# antenna.net
KiCad netlist of a schematic drawn in EAGLE
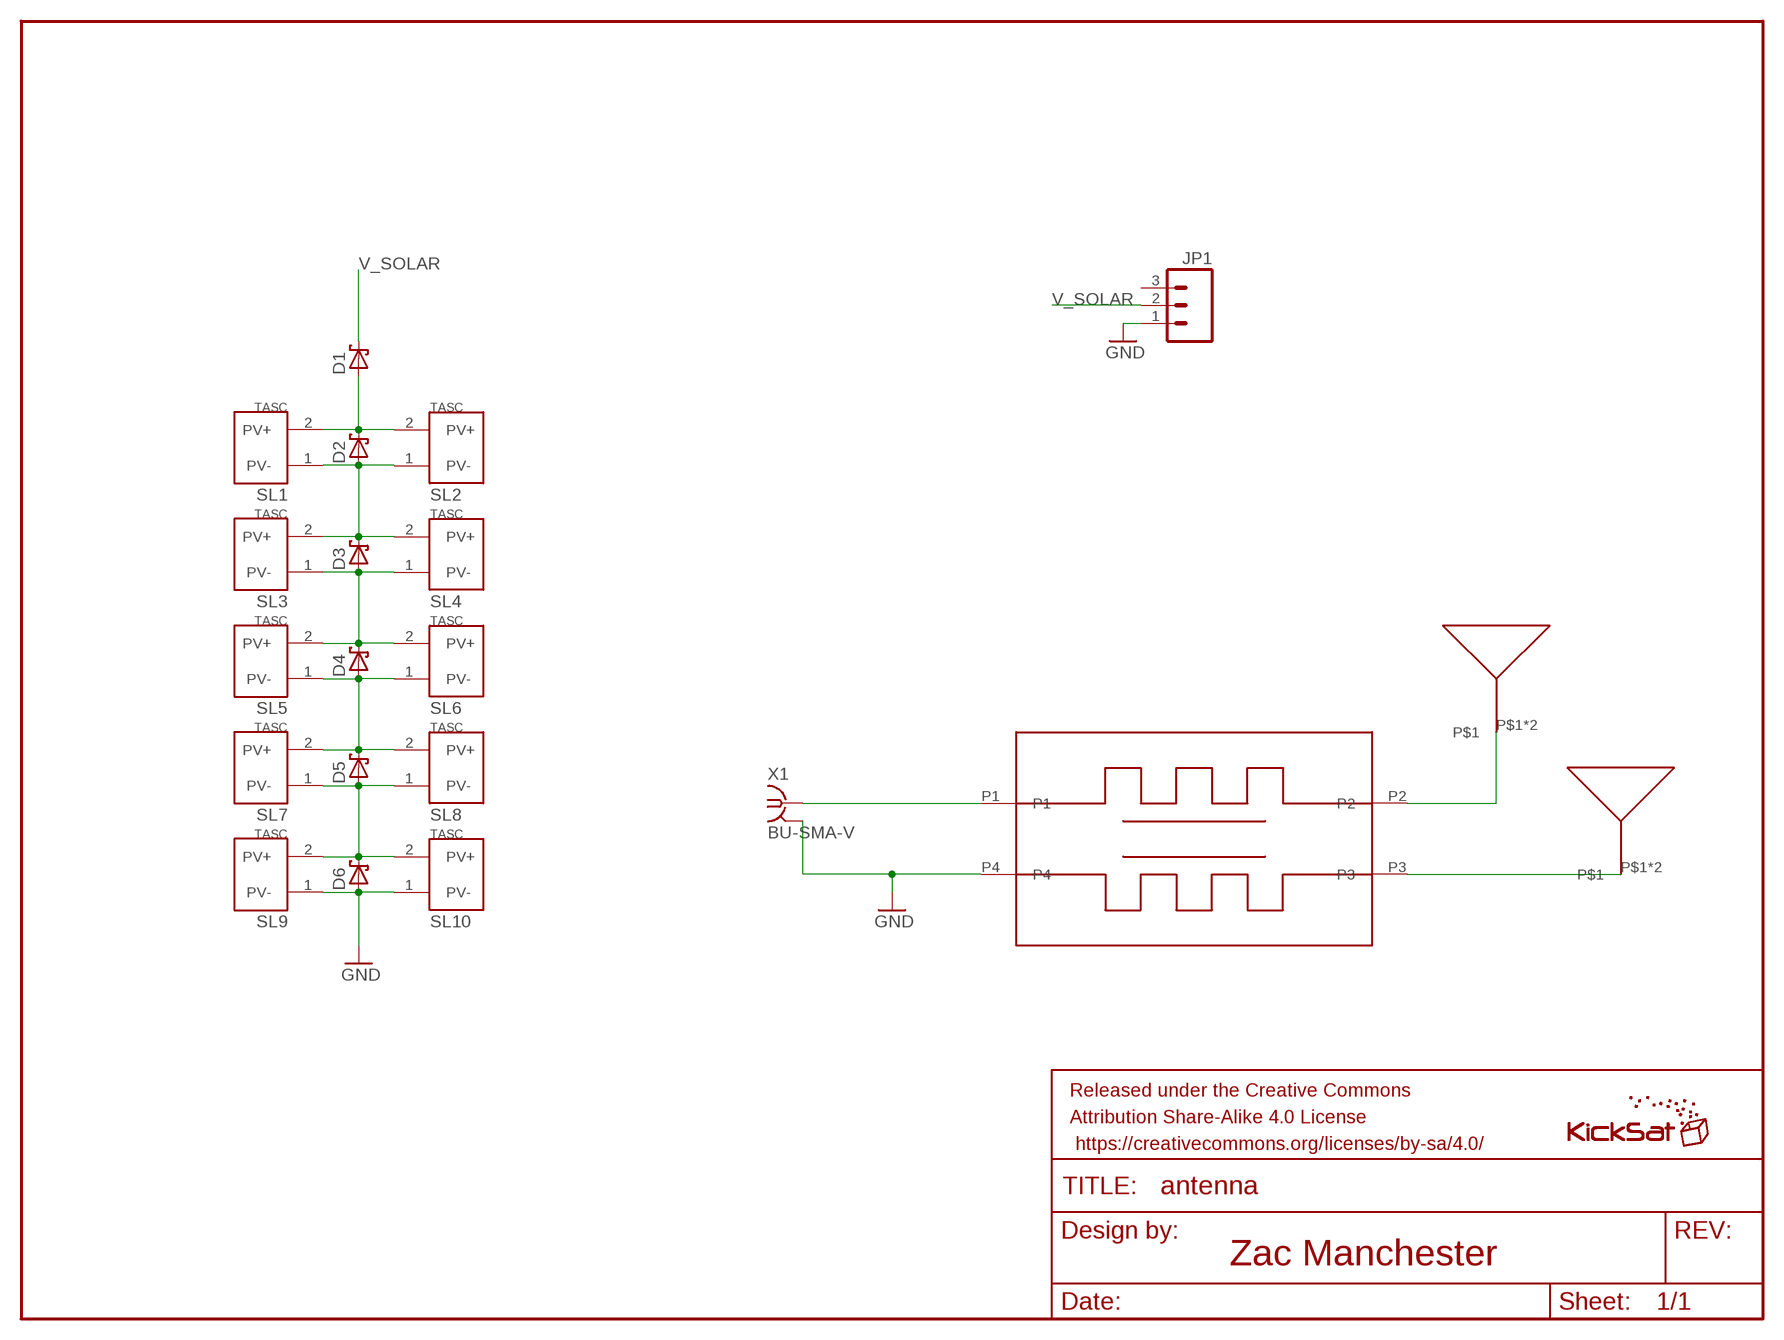
[diagram p0: schematic, sheet 1]

(export (version "E")
  (design (tool "Eeschema 10.0.6"))
  (components
    (comp (ref "B1")
      (value "BALUN")
      (footprint "eagle-import:BALUN")
      (libsource (lib "eagle-import") (part "BALUN"))
    )
    (comp (ref "D1")
      (value "SB_DIODE")
      (footprint "eagle-import:SB_DIODE")
      (libsource (lib "eagle-import") (part "SB_DIODE"))
    )
    (comp (ref "D2")
      (value "SB_DIODE")
      (footprint "eagle-import:SB_DIODE")
      (libsource (lib "eagle-import") (part "SB_DIODE"))
    )
    (comp (ref "D3")
      (value "SB_DIODE")
      (footprint "eagle-import:SB_DIODE")
      (libsource (lib "eagle-import") (part "SB_DIODE"))
    )
    (comp (ref "D4")
      (value "SB_DIODE")
      (footprint "eagle-import:SB_DIODE")
      (libsource (lib "eagle-import") (part "SB_DIODE"))
    )
    (comp (ref "D5")
      (value "SB_DIODE")
      (footprint "eagle-import:SB_DIODE")
      (libsource (lib "eagle-import") (part "SB_DIODE"))
    )
    (comp (ref "D6")
      (value "SB_DIODE")
      (footprint "eagle-import:SB_DIODE")
      (libsource (lib "eagle-import") (part "SB_DIODE"))
    )
    (comp (ref "FRAME1")
      (value "FRAME-LETTER")
      (footprint "eagle-import:CREATIVE_COMMONS")
      (libsource (lib "eagle-import") (part "FRAME-LETTER"))
    )
    (comp (ref "JP1")
      (value "M03POLAR_LOCK")
      (footprint "eagle-import:MOLEX-1X3_LOCK")
      (libsource (lib "eagle-import") (part "M03POLAR_LOCK"))
    )
    (comp (ref "SL1")
      (value "SOLAR_CELL")
      (footprint "eagle-import:SOLAR_CELL")
      (libsource (lib "eagle-import") (part "SOLAR_CELL"))
    )
    (comp (ref "SL2")
      (value "SOLAR_CELL")
      (footprint "eagle-import:SOLAR_CELL")
      (libsource (lib "eagle-import") (part "SOLAR_CELL"))
    )
    (comp (ref "SL3")
      (value "SOLAR_CELL")
      (footprint "eagle-import:SOLAR_CELL")
      (libsource (lib "eagle-import") (part "SOLAR_CELL"))
    )
    (comp (ref "SL4")
      (value "SOLAR_CELL")
      (footprint "eagle-import:SOLAR_CELL")
      (libsource (lib "eagle-import") (part "SOLAR_CELL"))
    )
    (comp (ref "SL5")
      (value "SOLAR_CELL")
      (footprint "eagle-import:SOLAR_CELL")
      (libsource (lib "eagle-import") (part "SOLAR_CELL"))
    )
    (comp (ref "SL6")
      (value "SOLAR_CELL")
      (footprint "eagle-import:SOLAR_CELL")
      (libsource (lib "eagle-import") (part "SOLAR_CELL"))
    )
    (comp (ref "SL7")
      (value "SOLAR_CELL")
      (footprint "eagle-import:SOLAR_CELL")
      (libsource (lib "eagle-import") (part "SOLAR_CELL"))
    )
    (comp (ref "SL8")
      (value "SOLAR_CELL")
      (footprint "eagle-import:SOLAR_CELL")
      (libsource (lib "eagle-import") (part "SOLAR_CELL"))
    )
    (comp (ref "SL9")
      (value "SOLAR_CELL")
      (footprint "eagle-import:SOLAR_CELL")
      (libsource (lib "eagle-import") (part "SOLAR_CELL"))
    )
    (comp (ref "SL10")
      (value "SOLAR_CELL")
      (footprint "eagle-import:SOLAR_CELL")
      (libsource (lib "eagle-import") (part "SOLAR_CELL"))
    )
    (comp (ref "U$1")
      (value "TAPEANTENNA")
      (footprint "eagle-import:TAPEANTENNA")
      (libsource (lib "eagle-import") (part "TAPEANTENNA"))
    )
    (comp (ref "U$2")
      (value "TAPEANTENNA")
      (footprint "eagle-import:TAPEANTENNA")
      (libsource (lib "eagle-import") (part "TAPEANTENNA"))
    )
    (comp (ref "U$3")
      (value "KICKSAT_LOGO")
      (footprint "eagle-import:KICKSAT_LOGO")
      (libsource (lib "eagle-import") (part "KICKSAT_LOGO"))
    )
    (comp (ref "X1")
      (value "BU-SMA-V")
      (footprint "eagle-import:BU-SMA-V")
      (libsource (lib "eagle-import") (part "BU-SMA-V"))
    )
  )
  (nets
    (net (code "1") (name "/V_SOLAR") (class "Default")
      (node (ref "D1") (pin "NEG") (pinfunction "NEG_NEG") (pintype "passive"))
      (node (ref "JP1") (pin "2") (pinfunction "2_2") (pintype "passive"))
    )
    (net (code "2") (name "GND") (class "Default")
      (node (ref "B1") (pin "P4") (pinfunction "P4_P4") (pintype "bidirectional"))
      (node (ref "D6") (pin "POS") (pinfunction "POS_POS") (pintype "passive"))
      (node (ref "JP1") (pin "1") (pinfunction "1_1") (pintype "passive"))
      (node (ref "SL10") (pin "1") (pinfunction "PV-_1") (pintype "bidirectional"))
      (node (ref "SL9") (pin "1") (pinfunction "PV-_1") (pintype "bidirectional"))
      (node (ref "X1") (pin "2") (pinfunction "2_2") (pintype "passive"))
      (node (ref "X1") (pin "3") (pinfunction "2_3") (pintype "passive"))
      (node (ref "X1") (pin "4") (pinfunction "2_4") (pintype "passive"))
      (node (ref "X1") (pin "5") (pinfunction "2_5") (pintype "passive"))
    )
    (net (code "3") (name "Net-(B1-PadP1)") (class "Default")
      (node (ref "B1") (pin "P1") (pinfunction "P1_P1") (pintype "bidirectional"))
      (node (ref "X1") (pin "1") (pinfunction "1_1") (pintype "passive"))
    )
    (net (code "4") (name "Net-(B1-PadP2)") (class "Default")
      (node (ref "B1") (pin "P2") (pinfunction "P2_P2") (pintype "bidirectional"))
      (node (ref "U$1") (pin "P$1") (pinfunction "P$1_P$1") (pintype "bidirectional"))
      (node (ref "U$1") (pin "P$2") (pinfunction "P$1_P$2") (pintype "bidirectional"))
    )
    (net (code "5") (name "Net-(B1-PadP3)") (class "Default")
      (node (ref "B1") (pin "P3") (pinfunction "P3_P3") (pintype "bidirectional"))
      (node (ref "U$2") (pin "P$1") (pinfunction "P$1_P$1") (pintype "bidirectional"))
      (node (ref "U$2") (pin "P$2") (pinfunction "P$1_P$2") (pintype "bidirectional"))
    )
    (net (code "6") (name "Net-(SL1-PV+)") (class "Default")
      (node (ref "D1") (pin "POS") (pinfunction "POS_POS") (pintype "passive"))
      (node (ref "D2") (pin "NEG") (pinfunction "NEG_NEG") (pintype "passive"))
      (node (ref "SL1") (pin "2") (pinfunction "PV+_2") (pintype "bidirectional"))
      (node (ref "SL2") (pin "2") (pinfunction "PV+_2") (pintype "bidirectional"))
    )
    (net (code "7") (name "Net-(SL1-PV-)") (class "Default")
      (node (ref "D2") (pin "POS") (pinfunction "POS_POS") (pintype "passive"))
      (node (ref "D3") (pin "NEG") (pinfunction "NEG_NEG") (pintype "passive"))
      (node (ref "SL1") (pin "1") (pinfunction "PV-_1") (pintype "bidirectional"))
      (node (ref "SL2") (pin "1") (pinfunction "PV-_1") (pintype "bidirectional"))
      (node (ref "SL3") (pin "2") (pinfunction "PV+_2") (pintype "bidirectional"))
      (node (ref "SL4") (pin "2") (pinfunction "PV+_2") (pintype "bidirectional"))
    )
    (net (code "8") (name "Net-(SL3-PV-)") (class "Default")
      (node (ref "D3") (pin "POS") (pinfunction "POS_POS") (pintype "passive"))
      (node (ref "D4") (pin "NEG") (pinfunction "NEG_NEG") (pintype "passive"))
      (node (ref "SL3") (pin "1") (pinfunction "PV-_1") (pintype "bidirectional"))
      (node (ref "SL4") (pin "1") (pinfunction "PV-_1") (pintype "bidirectional"))
      (node (ref "SL5") (pin "2") (pinfunction "PV+_2") (pintype "bidirectional"))
      (node (ref "SL6") (pin "2") (pinfunction "PV+_2") (pintype "bidirectional"))
    )
    (net (code "9") (name "Net-(SL5-PV-)") (class "Default")
      (node (ref "D4") (pin "POS") (pinfunction "POS_POS") (pintype "passive"))
      (node (ref "D5") (pin "NEG") (pinfunction "NEG_NEG") (pintype "passive"))
      (node (ref "SL5") (pin "1") (pinfunction "PV-_1") (pintype "bidirectional"))
      (node (ref "SL6") (pin "1") (pinfunction "PV-_1") (pintype "bidirectional"))
      (node (ref "SL7") (pin "2") (pinfunction "PV+_2") (pintype "bidirectional"))
      (node (ref "SL8") (pin "2") (pinfunction "PV+_2") (pintype "bidirectional"))
    )
    (net (code "10") (name "Net-(SL10-PV+)") (class "Default")
      (node (ref "D5") (pin "POS") (pinfunction "POS_POS") (pintype "passive"))
      (node (ref "D6") (pin "NEG") (pinfunction "NEG_NEG") (pintype "passive"))
      (node (ref "SL10") (pin "2") (pinfunction "PV+_2") (pintype "bidirectional"))
      (node (ref "SL7") (pin "1") (pinfunction "PV-_1") (pintype "bidirectional"))
      (node (ref "SL8") (pin "1") (pinfunction "PV-_1") (pintype "bidirectional"))
      (node (ref "SL9") (pin "2") (pinfunction "PV+_2") (pintype "bidirectional"))
    )
    (net (code "11") (name "unconnected-(JP1-Pad3)") (class "Default")
      (node (ref "JP1") (pin "3") (pinfunction "3_3") (pintype "passive"))
    )
  )
)
